# HVDCS_C8051F350_32TQFP.net
KiCad netlist of a schematic drawn in EAGLE
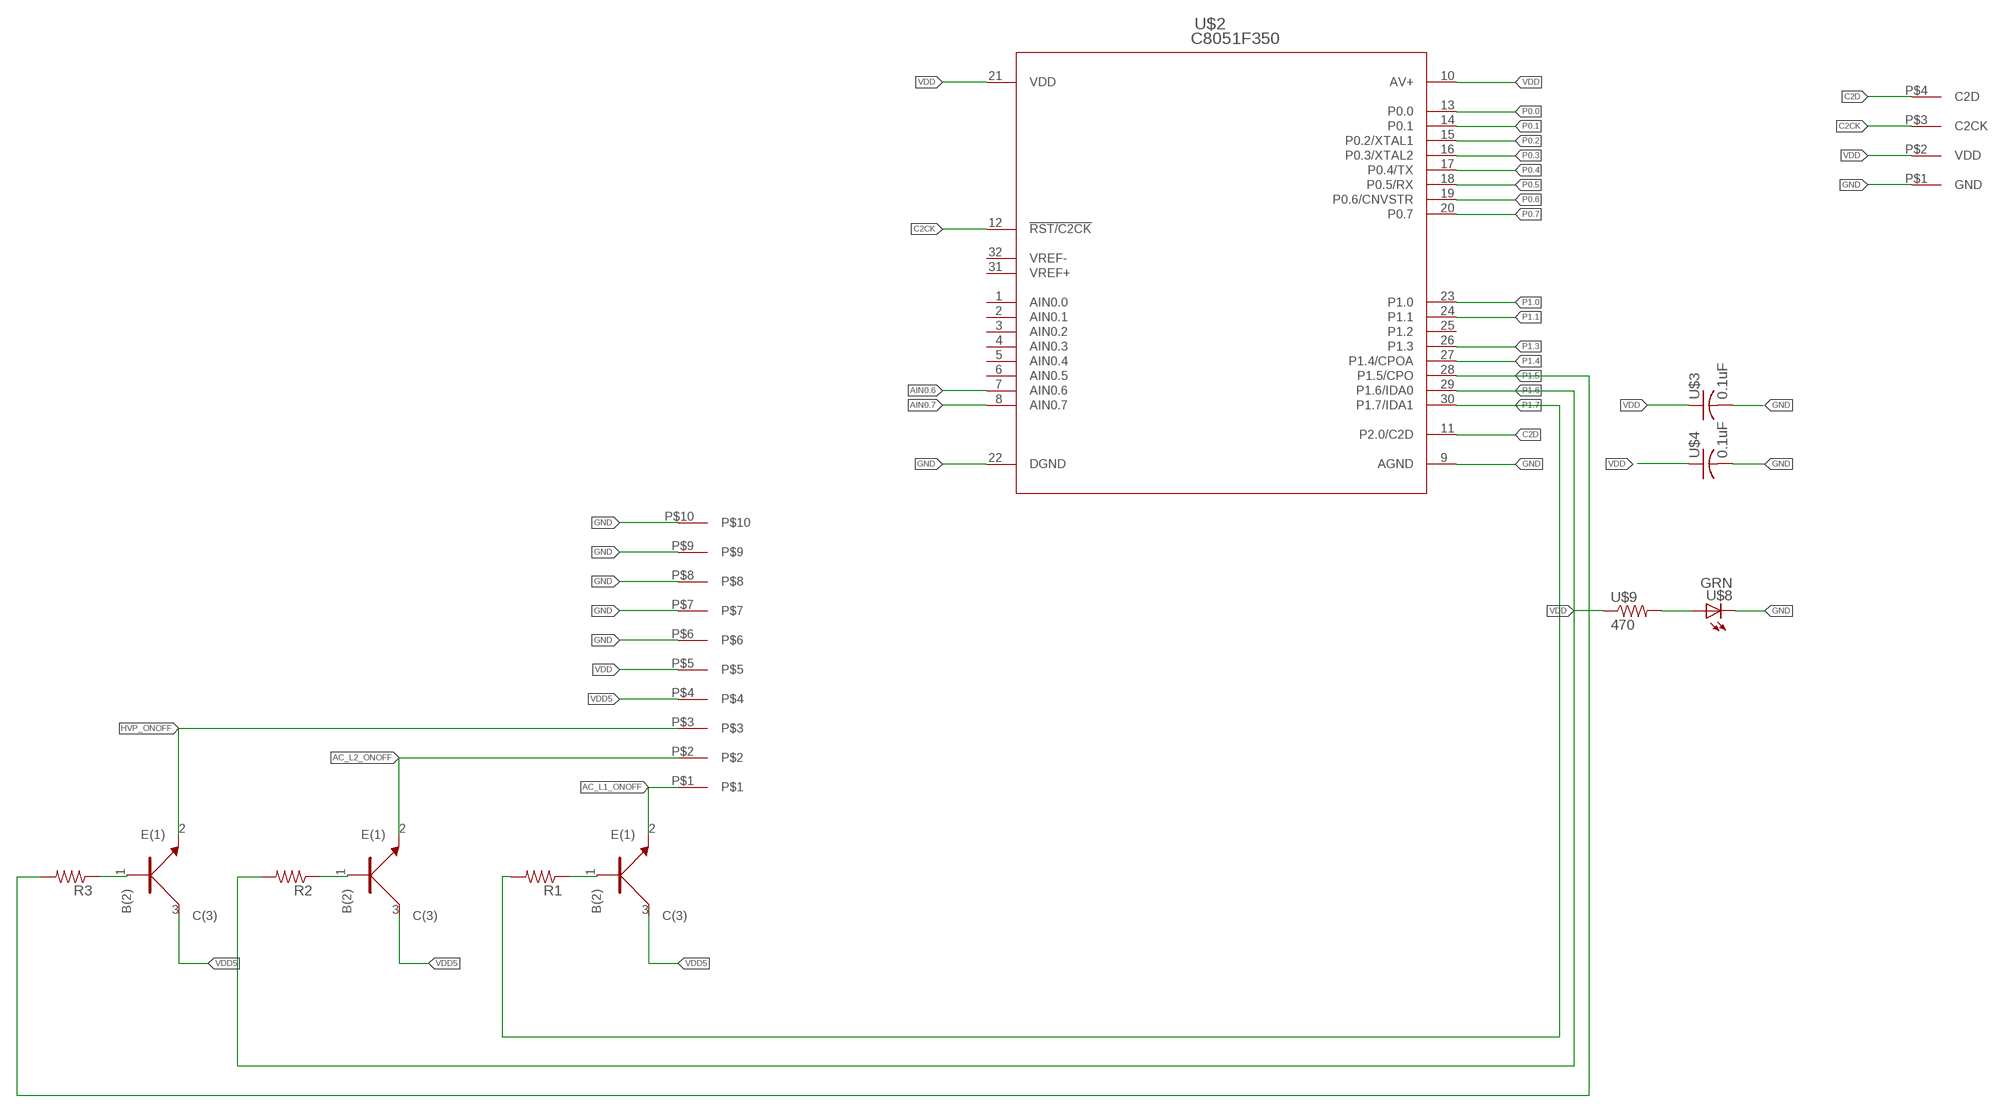
[diagram p0: schematic, sheet 1]

(export (version "E")
  (design (tool "Eeschema 10.0.6"))
  (components
    (comp (ref "R1")
      (value "R_0402")
      (footprint "eagle-import:0402")
      (libsource (lib "eagle-import") (part "R_0402"))
    )
    (comp (ref "R2")
      (value "R_0402")
      (footprint "eagle-import:0402")
      (libsource (lib "eagle-import") (part "R_0402"))
    )
    (comp (ref "R3")
      (value "R_0402")
      (footprint "eagle-import:0402")
      (libsource (lib "eagle-import") (part "R_0402"))
    )
    (comp (ref "U$2")
      (value "C8051F350")
      (footprint "eagle-import:QFP32-7X7-0P8MM")
      (libsource (lib "eagle-import") (part "C8051F350"))
    )
    (comp (ref "U$3")
      (value "C_0805_0.1UF")
      (footprint "eagle-import:C_0805_0.1UF")
      (libsource (lib "eagle-import") (part "C_0805_0.1UF"))
    )
    (comp (ref "U$4")
      (value "C_0805_0.1UF")
      (footprint "eagle-import:C_0805_0.1UF")
      (libsource (lib "eagle-import") (part "C_0805_0.1UF"))
    )
    (comp (ref "U$5")
      (value "1_X_10_HEADER_GENERIC_.1INCH")
      (footprint "eagle-import:HEADER_1_X_10_.1_INCH")
      (libsource (lib "eagle-import") (part "1_X_10_HEADER_GENERIC_.1INCH"))
    )
    (comp (ref "U$8")
      (value "LED_0805_GREEN")
      (footprint "eagle-import:LED_0805_GREEN")
      (libsource (lib "eagle-import") (part "LED_0805_GREEN"))
    )
    (comp (ref "U$9")
      (value "R_0805_470")
      (footprint "eagle-import:R_0805_470")
      (libsource (lib "eagle-import") (part "R_0805_470"))
    )
    (comp (ref "U$13")
      (value "C2D")
      (footprint "eagle-import:1X4_.1_INCH_HEADER")
      (libsource (lib "eagle-import") (part "C2D"))
    )
    (comp (ref "U1")
      (value "NPN")
      (footprint "eagle-import:SOT323")
      (fields (field (name "PARTNO") "BC846BW_NPN"))
      (libsource (lib "eagle-import") (part "BC846BW"))
    )
    (comp (ref "U2")
      (value "NPN")
      (footprint "eagle-import:SOT323")
      (fields (field (name "PARTNO") "BC846BW_NPN"))
      (libsource (lib "eagle-import") (part "BC846BW"))
    )
    (comp (ref "U3")
      (value "NPN")
      (footprint "eagle-import:SOT323")
      (fields (field (name "PARTNO") "BC846BW_NPN"))
      (libsource (lib "eagle-import") (part "BC846BW"))
    )
  )
  (nets
    (net (code "1") (name "AC_L1_ONOFF") (class "Default")
      (node (ref "U$5") (pin "P$1") (pinfunction "P$1_P$1") (pintype "bidirectional"))
      (node (ref "U1") (pin "2") (pinfunction "E(1)_2") (pintype "output"))
    )
    (net (code "2") (name "AC_L2_ONOFF") (class "Default")
      (node (ref "U$5") (pin "P$2") (pinfunction "P$2_P$2") (pintype "bidirectional"))
      (node (ref "U2") (pin "2") (pinfunction "E(1)_2") (pintype "output"))
    )
    (net (code "3") (name "AIN0.6") (class "Default")
      (node (ref "U$2") (pin "7") (pinfunction "AIN0.6_7") (pintype "passive"))
    )
    (net (code "4") (name "AIN0.7") (class "Default")
      (node (ref "U$2") (pin "8") (pinfunction "AIN0.7_8") (pintype "passive"))
    )
    (net (code "5") (name "C2CK") (class "Default")
      (node (ref "U$13") (pin "P$3") (pinfunction "C2CK_P$3") (pintype "bidirectional"))
      (node (ref "U$2") (pin "12") (pinfunction "~{RST/C2CK}_12") (pintype "passive"))
    )
    (net (code "6") (name "C2D") (class "Default")
      (node (ref "U$13") (pin "P$4") (pinfunction "C2D_P$4") (pintype "bidirectional"))
      (node (ref "U$2") (pin "11") (pinfunction "P2.0/C2D_11") (pintype "passive"))
    )
    (net (code "7") (name "GND") (class "Default")
      (node (ref "U$13") (pin "P$1") (pinfunction "GND_P$1") (pintype "bidirectional"))
      (node (ref "U$2") (pin "22") (pinfunction "DGND_22") (pintype "passive"))
      (node (ref "U$2") (pin "9") (pinfunction "AGND_9") (pintype "passive"))
      (node (ref "U$3") (pin "2") (pinfunction "2_2") (pintype "passive"))
      (node (ref "U$4") (pin "2") (pinfunction "2_2") (pintype "passive"))
      (node (ref "U$5") (pin "P$10") (pinfunction "P$10_P$10") (pintype "bidirectional"))
      (node (ref "U$5") (pin "P$6") (pinfunction "P$6_P$6") (pintype "bidirectional"))
      (node (ref "U$5") (pin "P$7") (pinfunction "P$7_P$7") (pintype "bidirectional"))
      (node (ref "U$5") (pin "P$8") (pinfunction "P$8_P$8") (pintype "bidirectional"))
      (node (ref "U$5") (pin "P$9") (pinfunction "P$9_P$9") (pintype "bidirectional"))
      (node (ref "U$8") (pin "C") (pinfunction "C_C") (pintype "passive"))
    )
    (net (code "8") (name "HVP_ONOFF") (class "Default")
      (node (ref "U$5") (pin "P$3") (pinfunction "P$3_P$3") (pintype "bidirectional"))
      (node (ref "U3") (pin "2") (pinfunction "E(1)_2") (pintype "output"))
    )
    (net (code "9") (name "Net-(R1-1)") (class "Default")
      (node (ref "R1") (pin "P$1") (pinfunction "1_P$1") (pintype "passive"))
      (node (ref "U1") (pin "1") (pinfunction "B(2)_1") (pintype "input"))
    )
    (net (code "10") (name "Net-(R2-1)") (class "Default")
      (node (ref "R2") (pin "P$1") (pinfunction "1_P$1") (pintype "passive"))
      (node (ref "U2") (pin "1") (pinfunction "B(2)_1") (pintype "input"))
    )
    (net (code "11") (name "Net-(R3-1)") (class "Default")
      (node (ref "R3") (pin "P$1") (pinfunction "1_P$1") (pintype "passive"))
      (node (ref "U3") (pin "1") (pinfunction "B(2)_1") (pintype "input"))
    )
    (net (code "12") (name "Net-(U$8-PadA)") (class "Default")
      (node (ref "U$8") (pin "A") (pinfunction "A_A") (pintype "passive"))
      (node (ref "U$9") (pin "2") (pinfunction "2_2") (pintype "passive"))
    )
    (net (code "13") (name "P0.0") (class "Default")
      (node (ref "U$2") (pin "13") (pinfunction "P0.0_13") (pintype "passive"))
    )
    (net (code "14") (name "P0.1") (class "Default")
      (node (ref "U$2") (pin "14") (pinfunction "P0.1_14") (pintype "passive"))
    )
    (net (code "15") (name "P0.2") (class "Default")
      (node (ref "U$2") (pin "15") (pinfunction "P0.2/XTAL1_15") (pintype "passive"))
    )
    (net (code "16") (name "P0.3") (class "Default")
      (node (ref "U$2") (pin "16") (pinfunction "P0.3/XTAL2_16") (pintype "passive"))
    )
    (net (code "17") (name "P0.4") (class "Default")
      (node (ref "U$2") (pin "17") (pinfunction "P0.4/TX_17") (pintype "passive"))
    )
    (net (code "18") (name "P0.5") (class "Default")
      (node (ref "U$2") (pin "18") (pinfunction "P0.5/RX_18") (pintype "passive"))
    )
    (net (code "19") (name "P0.6") (class "Default")
      (node (ref "U$2") (pin "19") (pinfunction "P0.6/CNVSTR_19") (pintype "passive"))
    )
    (net (code "20") (name "P0.7") (class "Default")
      (node (ref "U$2") (pin "20") (pinfunction "P0.7_20") (pintype "passive"))
    )
    (net (code "21") (name "P1.0") (class "Default")
      (node (ref "U$2") (pin "23") (pinfunction "P1.0_23") (pintype "passive"))
    )
    (net (code "22") (name "P1.1") (class "Default")
      (node (ref "U$2") (pin "24") (pinfunction "P1.1_24") (pintype "passive"))
    )
    (net (code "23") (name "P1.3") (class "Default")
      (node (ref "U$2") (pin "26") (pinfunction "P1.3_26") (pintype "passive"))
    )
    (net (code "24") (name "P1.4") (class "Default")
      (node (ref "U$2") (pin "27") (pinfunction "P1.4/CPOA_27") (pintype "passive"))
    )
    (net (code "25") (name "P1.5") (class "Default")
      (node (ref "R3") (pin "P$2") (pinfunction "2_P$2") (pintype "passive"))
      (node (ref "U$2") (pin "28") (pinfunction "P1.5/CPO_28") (pintype "passive"))
    )
    (net (code "26") (name "P1.6") (class "Default")
      (node (ref "R2") (pin "P$2") (pinfunction "2_P$2") (pintype "passive"))
      (node (ref "U$2") (pin "29") (pinfunction "P1.6/IDA0_29") (pintype "passive"))
    )
    (net (code "27") (name "P1.7") (class "Default")
      (node (ref "R1") (pin "P$2") (pinfunction "2_P$2") (pintype "passive"))
      (node (ref "U$2") (pin "30") (pinfunction "P1.7/IDA1_30") (pintype "passive"))
    )
    (net (code "28") (name "VDD") (class "Default")
      (node (ref "U$13") (pin "P$2") (pinfunction "VDD_P$2") (pintype "bidirectional"))
      (node (ref "U$2") (pin "10") (pinfunction "AV+_10") (pintype "passive"))
      (node (ref "U$2") (pin "21") (pinfunction "VDD_21") (pintype "passive"))
      (node (ref "U$3") (pin "1") (pinfunction "1_1") (pintype "passive"))
      (node (ref "U$4") (pin "1") (pinfunction "1_1") (pintype "passive"))
      (node (ref "U$5") (pin "P$5") (pinfunction "P$5_P$5") (pintype "bidirectional"))
      (node (ref "U$9") (pin "1") (pinfunction "1_1") (pintype "passive"))
    )
    (net (code "29") (name "VDD5") (class "Default")
      (node (ref "U$5") (pin "P$4") (pinfunction "P$4_P$4") (pintype "bidirectional"))
      (node (ref "U1") (pin "3") (pinfunction "C(3)_3") (pintype "input"))
      (node (ref "U2") (pin "3") (pinfunction "C(3)_3") (pintype "input"))
      (node (ref "U3") (pin "3") (pinfunction "C(3)_3") (pintype "input"))
    )
    (net (code "30") (name "unconnected-(U$2-AIN0.0-Pad1)") (class "Default")
      (node (ref "U$2") (pin "1") (pinfunction "AIN0.0_1") (pintype "passive"))
    )
    (net (code "31") (name "unconnected-(U$2-AIN0.1-Pad2)") (class "Default")
      (node (ref "U$2") (pin "2") (pinfunction "AIN0.1_2") (pintype "passive"))
    )
    (net (code "32") (name "unconnected-(U$2-AIN0.2-Pad3)") (class "Default")
      (node (ref "U$2") (pin "3") (pinfunction "AIN0.2_3") (pintype "passive"))
    )
    (net (code "33") (name "unconnected-(U$2-AIN0.3-Pad4)") (class "Default")
      (node (ref "U$2") (pin "4") (pinfunction "AIN0.3_4") (pintype "passive"))
    )
    (net (code "34") (name "unconnected-(U$2-AIN0.4-Pad5)") (class "Default")
      (node (ref "U$2") (pin "5") (pinfunction "AIN0.4_5") (pintype "passive"))
    )
    (net (code "35") (name "unconnected-(U$2-AIN0.5-Pad6)") (class "Default")
      (node (ref "U$2") (pin "6") (pinfunction "AIN0.5_6") (pintype "passive"))
    )
    (net (code "36") (name "unconnected-(U$2-P1.2-Pad25)") (class "Default")
      (node (ref "U$2") (pin "25") (pinfunction "P1.2_25") (pintype "passive"))
    )
    (net (code "37") (name "unconnected-(U$2-VREF+-Pad31)") (class "Default")
      (node (ref "U$2") (pin "31") (pinfunction "VREF+_31") (pintype "passive"))
    )
    (net (code "38") (name "unconnected-(U$2-VREF--Pad32)") (class "Default")
      (node (ref "U$2") (pin "32") (pinfunction "VREF-_32") (pintype "passive"))
    )
  )
)
